# MySens-GWeasyRS485-Nano-005.net
KiCad netlist of a schematic drawn in EAGLE
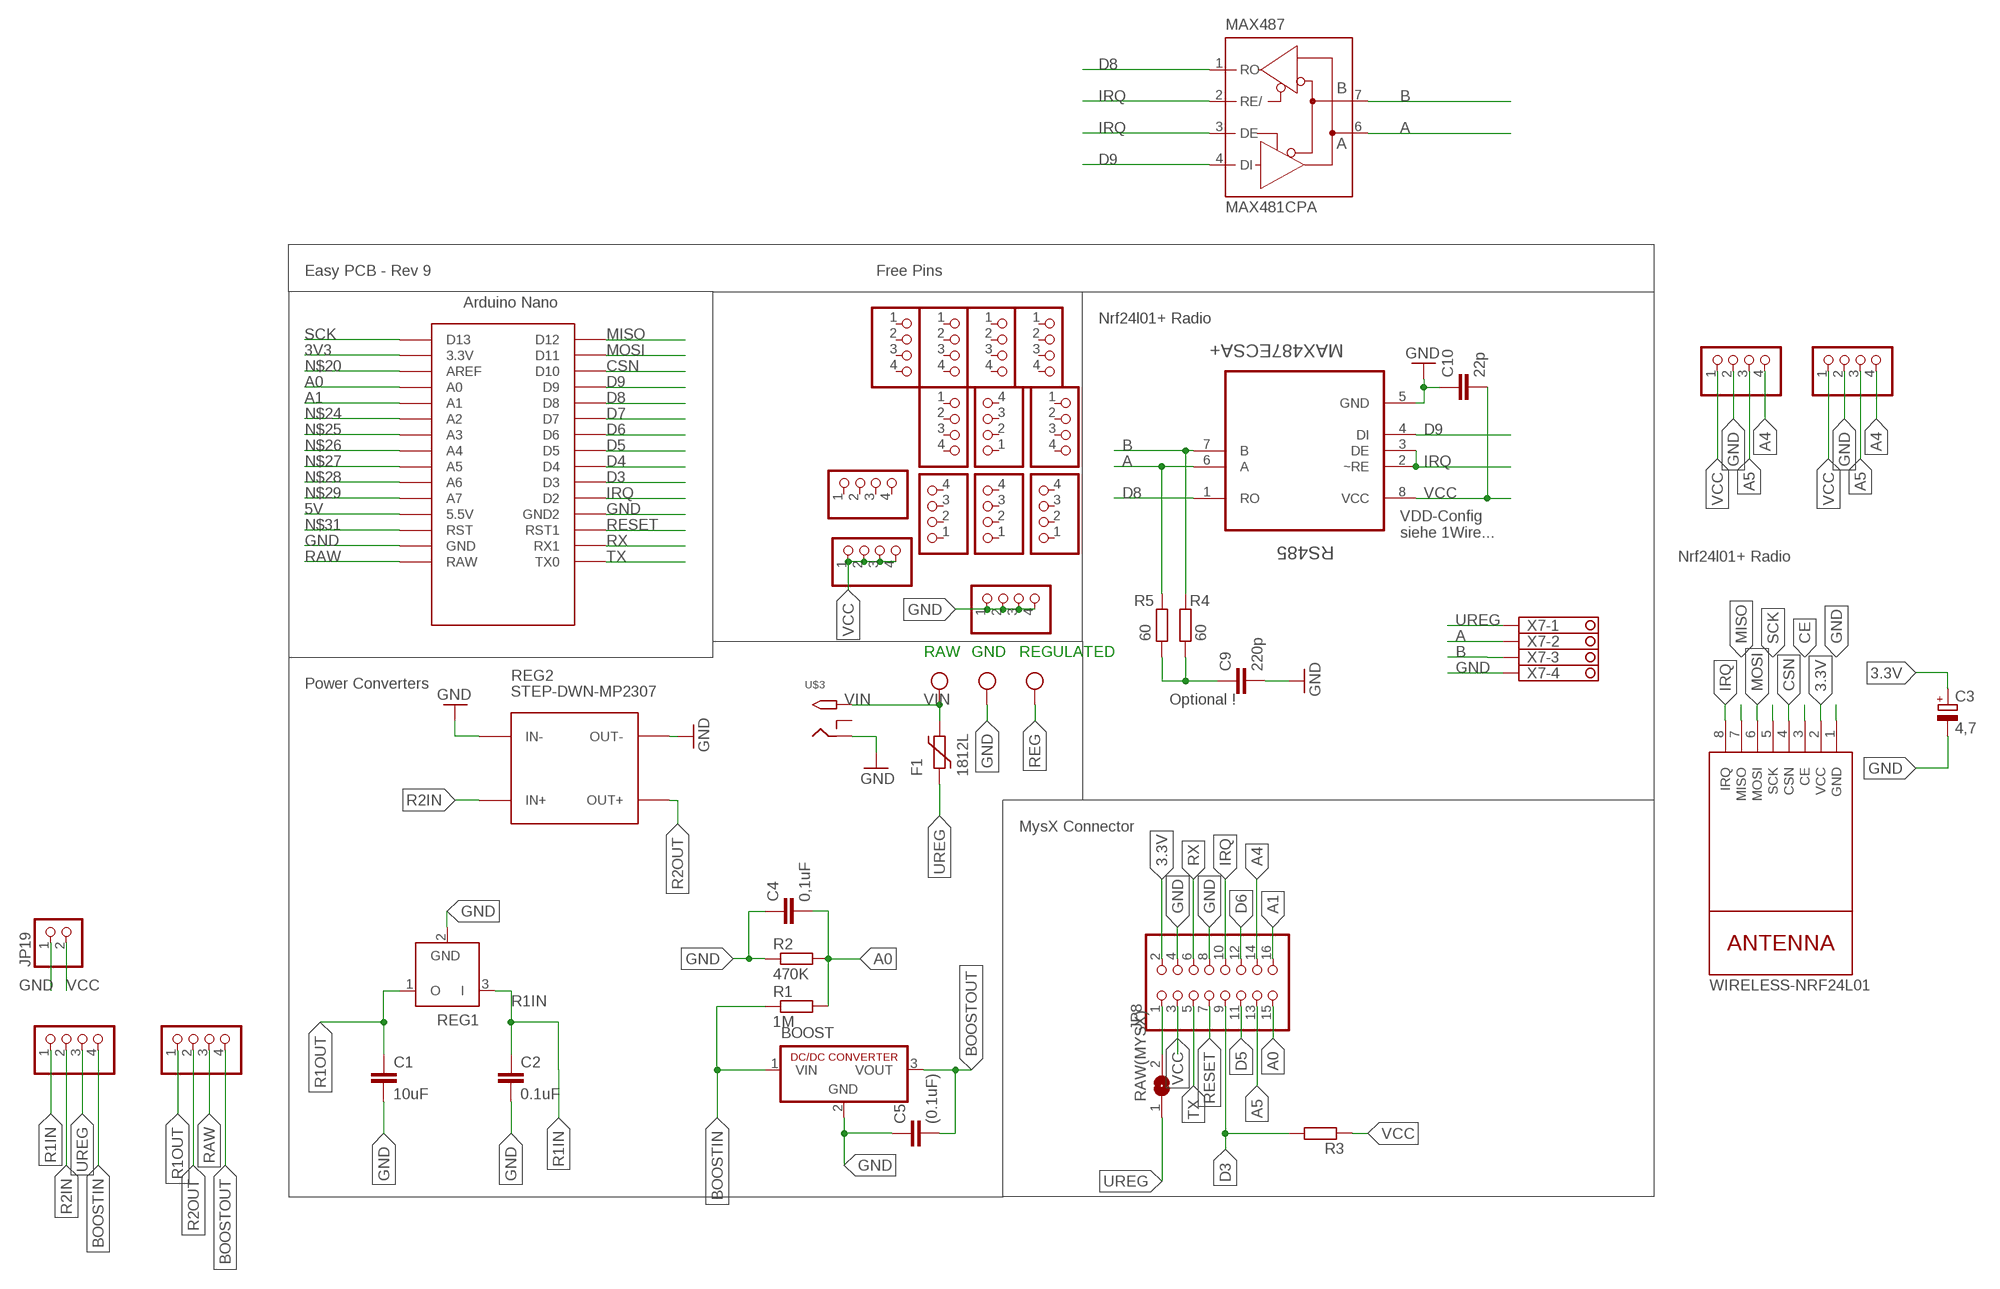
[diagram p0: schematic, sheet 1]

(export (version "E")
  (design (tool "Eeschema 10.0.6"))
  (components
    (comp (ref "BOOST")
      (value "R-78C1.8-1.0")
      (footprint "eagle-import:SIP3")
      (libsource (lib "eagle-import") (part "R-78C-1.01.8"))
    )
    (comp (ref "C1")
      (value "10uF")
      (footprint "eagle-import:C1210")
      (libsource (lib "eagle-import") (part "C-EUC1210"))
    )
    (comp (ref "C2")
      (value "0.1uF")
      (footprint "eagle-import:C1206")
      (libsource (lib "eagle-import") (part "C-EUC1206"))
    )
    (comp (ref "C3")
      (value "4,7")
      (footprint "eagle-import:SMC_C")
      (libsource (lib "eagle-import") (part "CPOL-EUSMCC"))
    )
    (comp (ref "C4")
      (value "0,1uF")
      (footprint "eagle-import:C1206")
      (libsource (lib "eagle-import") (part "C-EUC1206"))
    )
    (comp (ref "C5")
      (value "(0.1uF)")
      (footprint "eagle-import:C1206")
      (libsource (lib "eagle-import") (part "C-EUC1206"))
    )
    (comp (ref "C9")
      (value "220p")
      (footprint "eagle-import:C0805")
      (libsource (lib "eagle-import") (part "C-EUC0805"))
    )
    (comp (ref "C10")
      (value "22p")
      (footprint "eagle-import:C0805")
      (libsource (lib "eagle-import") (part "C-EUC0805"))
    )
    (comp (ref "F1")
      (value "1812L")
      (footprint "eagle-import:1812L")
      (libsource (lib "eagle-import") (part "1812L"))
    )
    (comp (ref "JP1")
      (value "PINHD-1X04_2.54-S")
      (footprint "eagle-import:1X04-S")
      (libsource (lib "eagle-import") (part "PINHD-1X04_2.54-S"))
    )
    (comp (ref "JP2")
      (value "PINHD-1X04_2.54-S")
      (footprint "eagle-import:1X04-S")
      (libsource (lib "eagle-import") (part "PINHD-1X04_2.54-S"))
    )
    (comp (ref "JP3")
      (value "PINHD-1X04_2.54-S")
      (footprint "eagle-import:1X04-S")
      (libsource (lib "eagle-import") (part "PINHD-1X04_2.54-S"))
    )
    (comp (ref "JP4")
      (value "PINHD-1X04_2.54-S")
      (footprint "eagle-import:1X04-S")
      (libsource (lib "eagle-import") (part "PINHD-1X04_2.54-S"))
    )
    (comp (ref "JP5")
      (value "PINHD-1X04_2.54-S")
      (footprint "eagle-import:1X04-S")
      (libsource (lib "eagle-import") (part "PINHD-1X04_2.54-S"))
    )
    (comp (ref "JP6")
      (value "PINHD-1X04_2.54-S")
      (footprint "eagle-import:1X04-S")
      (libsource (lib "eagle-import") (part "PINHD-1X04_2.54-S"))
    )
    (comp (ref "JP7")
      (value "PINHD-1X04_2.54-S")
      (footprint "eagle-import:1X04-S")
      (libsource (lib "eagle-import") (part "PINHD-1X04_2.54-S"))
    )
    (comp (ref "JP8")
      (value "PINHD-2X08_2.54")
      (footprint "eagle-import:2X08")
      (libsource (lib "eagle-import") (part "PINHD-2X08_2.54"))
    )
    (comp (ref "JP9")
      (value "PINHD-1X04_2.54-S")
      (footprint "eagle-import:1X04-S")
      (libsource (lib "eagle-import") (part "PINHD-1X04_2.54-S"))
    )
    (comp (ref "JP10")
      (value "PINHD-1X04_2.54-S")
      (footprint "eagle-import:1X04-S")
      (libsource (lib "eagle-import") (part "PINHD-1X04_2.54-S"))
    )
    (comp (ref "JP11")
      (value "PINHD-1X04_2.54-S")
      (footprint "eagle-import:1X04-S")
      (libsource (lib "eagle-import") (part "PINHD-1X04_2.54-S"))
    )
    (comp (ref "JP12")
      (value "PINHD-1X04_2.54-S")
      (footprint "eagle-import:1X04-S")
      (libsource (lib "eagle-import") (part "PINHD-1X04_2.54-S"))
    )
    (comp (ref "JP13")
      (value "PINHD-1X04_2.54-S")
      (footprint "eagle-import:1X04-S")
      (libsource (lib "eagle-import") (part "PINHD-1X04_2.54-S"))
    )
    (comp (ref "JP14")
      (value "PINHD-1X04_2.54-S")
      (footprint "eagle-import:1X04-S")
      (libsource (lib "eagle-import") (part "PINHD-1X04_2.54-S"))
    )
    (comp (ref "JP15")
      (value "PINHD-1X04_2.54-S")
      (footprint "eagle-import:1X04-S")
      (libsource (lib "eagle-import") (part "PINHD-1X04_2.54-S"))
    )
    (comp (ref "JP16")
      (value "PINHD-1X04_2.54-S")
      (footprint "eagle-import:1X04-S")
      (libsource (lib "eagle-import") (part "PINHD-1X04_2.54-S"))
    )
    (comp (ref "JP17")
      (value "PINHD-1X04_2.54-S")
      (footprint "eagle-import:1X04-S")
      (libsource (lib "eagle-import") (part "PINHD-1X04_2.54-S"))
    )
    (comp (ref "JP18")
      (value "PINHD-1X04_2.54-S")
      (footprint "eagle-import:1X04-S")
      (libsource (lib "eagle-import") (part "PINHD-1X04_2.54-S"))
    )
    (comp (ref "JP19")
      (value "PINHD-1X2")
      (footprint "eagle-import:1X02")
      (libsource (lib "eagle-import") (part "PINHD-1X2"))
    )
    (comp (ref "MAX487")
      (value "MAX481CPA")
      (footprint "eagle-import:DIL08")
      (libsource (lib "eagle-import") (part "MAX481CPA"))
    )
    (comp (ref "NRF24L01+")
      (value "WIRELESS-NRF24L01")
      (footprint "eagle-import:WIRELESS-NRF24L01")
      (libsource (lib "eagle-import") (part "WIRELESS-NRF24L01"))
    )
    (comp (ref "R1")
      (value "1M")
      (footprint "eagle-import:R0805")
      (libsource (lib "eagle-import") (part "R-EU_R0805"))
    )
    (comp (ref "R2")
      (value "470K")
      (footprint "eagle-import:R0805")
      (libsource (lib "eagle-import") (part "R-EU_R0805"))
    )
    (comp (ref "R3")
      (value "R-EU_R0805")
      (footprint "eagle-import:R0805")
      (libsource (lib "eagle-import") (part "R-EU_R0805"))
    )
    (comp (ref "R4")
      (value "60")
      (footprint "eagle-import:R0805")
      (libsource (lib "eagle-import") (part "R-EU_R0805"))
    )
    (comp (ref "R5")
      (value "60")
      (footprint "eagle-import:R0805")
      (libsource (lib "eagle-import") (part "R-EU_R0805"))
    )
    (comp (ref "RAW(MYSX)")
      (value "SJ")
      (footprint "eagle-import:SJ")
      (libsource (lib "eagle-import") (part "SJ"))
    )
    (comp (ref "REG1")
      (value "LP2950Z")
      (footprint "eagle-import:TO92")
      (libsource (lib "eagle-import") (part "LP2950Z"))
    )
    (comp (ref "REG2")
      (value "STEP-DWN-MP2307")
      (footprint "eagle-import:DC-DC-STEP-DOWN-MP2307")
      (libsource (lib "eagle-import") (part "DC-DC-STEP-DOWN-MP2307"))
    )
    (comp (ref "REGULATED")
      (value "W237-103")
      (footprint "eagle-import:W237-103")
      (fields (field (name "MPN") "237-103"))
      (libsource (lib "eagle-import") (part "W237-103"))
    )
    (comp (ref "RS485")
      (value "MAX487ECSA+")
      (footprint "eagle-import:SOIC127P600X175-8N")
      (libsource (lib "eagle-import") (part "MAX487ECSA+"))
    )
    (comp (ref "U$2")
      (value "NANO")
      (footprint "eagle-import:NANO")
      (libsource (lib "eagle-import") (part "NANO"))
    )
    (comp (ref "U$3")
      (value "2.1MMJACKTHM")
      (footprint "eagle-import:PJ-102A")
      (libsource (lib "eagle-import") (part "2.1MMJACKTHM"))
    )
    (comp (ref "X7")
      (value "1751264")
      (footprint "eagle-import:1751264")
      (libsource (lib "eagle-import") (part "1751264"))
    )
  )
  (nets
    (net (code "1") (name "/3V3") (class "Default")
      (node (ref "U$2") (pin "3.3V") (pinfunction "3.3V_3.3V") (pintype "bidirectional"))
    )
    (net (code "2") (name "/5V") (class "Default")
      (node (ref "U$2") (pin "5V") (pinfunction "5.5V_5V") (pintype "bidirectional"))
    )
    (net (code "3") (name "/A") (class "Default")
      (node (ref "MAX487") (pin "6") (pinfunction "A_6") (pintype "passive"))
      (node (ref "R5") (pin "2") (pinfunction "2_2") (pintype "passive"))
      (node (ref "RS485") (pin "6") (pinfunction "A_6") (pintype "bidirectional"))
      (node (ref "X7") (pin "2") (pinfunction "K_2") (pintype "passive"))
    )
    (net (code "4") (name "/B") (class "Default")
      (node (ref "MAX487") (pin "7") (pinfunction "B_7") (pintype "passive"))
      (node (ref "R4") (pin "2") (pinfunction "2_2") (pintype "passive"))
      (node (ref "RS485") (pin "7") (pinfunction "B_7") (pintype "bidirectional"))
      (node (ref "X7") (pin "3") (pinfunction "K_3") (pintype "passive"))
    )
    (net (code "5") (name "/D4") (class "Default")
      (node (ref "U$2") (pin "D4") (pinfunction "D4_D4") (pintype "bidirectional"))
    )
    (net (code "6") (name "/D7") (class "Default")
      (node (ref "U$2") (pin "D7") (pinfunction "D7_D7") (pintype "bidirectional"))
    )
    (net (code "7") (name "/D8") (class "Default")
      (node (ref "MAX487") (pin "1") (pinfunction "RO_1") (pintype "output"))
      (node (ref "RS485") (pin "1") (pinfunction "RO_1") (pintype "output"))
      (node (ref "U$2") (pin "D8") (pinfunction "D8_D8") (pintype "bidirectional"))
    )
    (net (code "8") (name "/D9") (class "Default")
      (node (ref "MAX487") (pin "4") (pinfunction "DI_4") (pintype "input"))
      (node (ref "RS485") (pin "4") (pinfunction "DI_4") (pintype "input"))
      (node (ref "U$2") (pin "D9") (pinfunction "D9_D9") (pintype "bidirectional"))
    )
    (net (code "9") (name "/N$20") (class "Default")
      (node (ref "U$2") (pin "AREF") (pinfunction "AREF_AREF") (pintype "bidirectional"))
    )
    (net (code "10") (name "/N$24") (class "Default")
      (node (ref "U$2") (pin "A2") (pinfunction "A2_A2") (pintype "bidirectional"))
    )
    (net (code "11") (name "/N$25") (class "Default")
      (node (ref "U$2") (pin "A3") (pinfunction "A3_A3") (pintype "bidirectional"))
    )
    (net (code "12") (name "/N$26") (class "Default")
      (node (ref "U$2") (pin "A4") (pinfunction "A4_A4") (pintype "bidirectional"))
    )
    (net (code "13") (name "/N$27") (class "Default")
      (node (ref "U$2") (pin "A5") (pinfunction "A5_A5") (pintype "bidirectional"))
    )
    (net (code "14") (name "/N$28") (class "Default")
      (node (ref "U$2") (pin "A6") (pinfunction "A6_A6") (pintype "bidirectional"))
    )
    (net (code "15") (name "/N$29") (class "Default")
      (node (ref "U$2") (pin "A7") (pinfunction "A7_A7") (pintype "bidirectional"))
    )
    (net (code "16") (name "/N$31") (class "Default")
      (node (ref "U$2") (pin "RST") (pinfunction "RST_RST") (pintype "bidirectional"))
    )
    (net (code "17") (name "/VIN") (class "Default")
      (node (ref "F1") (pin "P$2") (pinfunction "2_P$2") (pintype "passive"))
      (node (ref "REGULATED") (pin "3") (pinfunction "KL_3") (pintype "passive"))
      (node (ref "U$3") (pin "TIP") (pinfunction "TIP_TIP") (pintype "bidirectional"))
    )
    (net (code "18") (name "3.3V") (class "Default")
      (node (ref "C3") (pin "+") (pinfunction "+_+") (pintype "passive"))
      (node (ref "JP8") (pin "2") (pinfunction "2_2") (pintype "passive"))
      (node (ref "NRF24L01+") (pin "2") (pinfunction "VCC_2") (pintype "power_in"))
    )
    (net (code "19") (name "A0") (class "Default")
      (node (ref "C4") (pin "2") (pinfunction "2_2") (pintype "passive"))
      (node (ref "JP8") (pin "15") (pinfunction "15_15") (pintype "passive"))
      (node (ref "R1") (pin "2") (pinfunction "2_2") (pintype "passive"))
      (node (ref "R2") (pin "2") (pinfunction "2_2") (pintype "passive"))
      (node (ref "U$2") (pin "A0") (pinfunction "A0_A0") (pintype "bidirectional"))
    )
    (net (code "20") (name "A1") (class "Default")
      (node (ref "JP8") (pin "16") (pinfunction "16_16") (pintype "passive"))
      (node (ref "U$2") (pin "A1") (pinfunction "A1_A1") (pintype "bidirectional"))
    )
    (net (code "21") (name "A4") (class "Default")
      (node (ref "JP10") (pin "4") (pinfunction "4_4") (pintype "passive"))
      (node (ref "JP6") (pin "4") (pinfunction "4_4") (pintype "passive"))
      (node (ref "JP8") (pin "14") (pinfunction "14_14") (pintype "passive"))
    )
    (net (code "22") (name "A5") (class "Default")
      (node (ref "JP10") (pin "3") (pinfunction "3_3") (pintype "passive"))
      (node (ref "JP6") (pin "3") (pinfunction "3_3") (pintype "passive"))
      (node (ref "JP8") (pin "13") (pinfunction "13_13") (pintype "passive"))
    )
    (net (code "23") (name "BOOSTIN") (class "Default")
      (node (ref "BOOST") (pin "1") (pinfunction "VIN_1") (pintype "passive"))
      (node (ref "JP2") (pin "4") (pinfunction "4_4") (pintype "passive"))
      (node (ref "R1") (pin "1") (pinfunction "1_1") (pintype "passive"))
    )
    (net (code "24") (name "BOOSTOUT") (class "Default")
      (node (ref "BOOST") (pin "3") (pinfunction "VOUT_3") (pintype "passive"))
      (node (ref "C5") (pin "2") (pinfunction "2_2") (pintype "passive"))
      (node (ref "JP4") (pin "4") (pinfunction "4_4") (pintype "passive"))
    )
    (net (code "25") (name "CE") (class "Default")
      (node (ref "NRF24L01+") (pin "3") (pinfunction "CE_3") (pintype "bidirectional"))
    )
    (net (code "26") (name "CSN") (class "Default")
      (node (ref "NRF24L01+") (pin "4") (pinfunction "CSN_4") (pintype "bidirectional"))
      (node (ref "U$2") (pin "D10") (pinfunction "D10_D10") (pintype "bidirectional"))
    )
    (net (code "27") (name "D3") (class "Default")
      (node (ref "JP8") (pin "9") (pinfunction "9_9") (pintype "passive"))
      (node (ref "R3") (pin "2") (pinfunction "2_2") (pintype "passive"))
      (node (ref "U$2") (pin "D3") (pinfunction "D3_D3") (pintype "bidirectional"))
    )
    (net (code "28") (name "D5") (class "Default")
      (node (ref "JP8") (pin "11") (pinfunction "11_11") (pintype "passive"))
      (node (ref "U$2") (pin "D5") (pinfunction "D5_D5") (pintype "bidirectional"))
    )
    (net (code "29") (name "D6") (class "Default")
      (node (ref "JP8") (pin "12") (pinfunction "12_12") (pintype "passive"))
      (node (ref "U$2") (pin "D6") (pinfunction "D6_D6") (pintype "bidirectional"))
    )
    (net (code "30") (name "GND") (class "Default")
      (node (ref "BOOST") (pin "2") (pinfunction "GND_2") (pintype "passive"))
      (node (ref "C1") (pin "2") (pinfunction "2_2") (pintype "passive"))
      (node (ref "C10") (pin "1") (pinfunction "1_1") (pintype "passive"))
      (node (ref "C2") (pin "2") (pinfunction "2_2") (pintype "passive"))
      (node (ref "C3") (pin "-") (pinfunction "-_-") (pintype "passive"))
      (node (ref "C4") (pin "1") (pinfunction "1_1") (pintype "passive"))
      (node (ref "C5") (pin "1") (pinfunction "1_1") (pintype "passive"))
      (node (ref "C9") (pin "2") (pinfunction "2_2") (pintype "passive"))
      (node (ref "JP1") (pin "1") (pinfunction "1_1") (pintype "passive"))
      (node (ref "JP1") (pin "2") (pinfunction "2_2") (pintype "passive"))
      (node (ref "JP1") (pin "3") (pinfunction "3_3") (pintype "passive"))
      (node (ref "JP1") (pin "4") (pinfunction "4_4") (pintype "passive"))
      (node (ref "JP10") (pin "2") (pinfunction "2_2") (pintype "passive"))
      (node (ref "JP19") (pin "1") (pinfunction "1_1") (pintype "passive"))
      (node (ref "JP6") (pin "2") (pinfunction "2_2") (pintype "passive"))
      (node (ref "JP8") (pin "4") (pinfunction "4_4") (pintype "passive"))
      (node (ref "JP8") (pin "8") (pinfunction "8_8") (pintype "passive"))
      (node (ref "NRF24L01+") (pin "1") (pinfunction "GND_1") (pintype "power_in"))
      (node (ref "R2") (pin "1") (pinfunction "1_1") (pintype "passive"))
      (node (ref "REG1") (pin "2") (pinfunction "GND_2") (pintype "power_in"))
      (node (ref "REG2") (pin "IN-") (pinfunction "IN-_IN-") (pintype "bidirectional"))
      (node (ref "REG2") (pin "OUT-") (pinfunction "OUT-_OUT-") (pintype "bidirectional"))
      (node (ref "REGULATED") (pin "2") (pinfunction "KL_2") (pintype "passive"))
      (node (ref "RS485") (pin "5") (pinfunction "GND_5") (pintype "passive"))
      (node (ref "U$2") (pin "GND") (pinfunction "GND_GND") (pintype "bidirectional"))
      (node (ref "U$2") (pin "GND1") (pinfunction "GND2_GND1") (pintype "bidirectional"))
      (node (ref "U$3") (pin "RING") (pinfunction "RING_RING") (pintype "bidirectional"))
      (node (ref "X7") (pin "4") (pinfunction "K_4") (pintype "passive"))
    )
    (net (code "31") (name "IRQ") (class "Default")
      (node (ref "JP8") (pin "10") (pinfunction "10_10") (pintype "passive"))
      (node (ref "MAX487") (pin "2") (pinfunction "RE/_2") (pintype "input"))
      (node (ref "MAX487") (pin "3") (pinfunction "DE_3") (pintype "input"))
      (node (ref "NRF24L01+") (pin "8") (pinfunction "IRQ_8") (pintype "bidirectional"))
      (node (ref "RS485") (pin "2") (pinfunction "~{RE}_2") (pintype "input"))
      (node (ref "RS485") (pin "3") (pinfunction "DE_3") (pintype "input"))
      (node (ref "U$2") (pin "D2") (pinfunction "D2_D2") (pintype "bidirectional"))
    )
    (net (code "32") (name "MISO") (class "Default")
      (node (ref "NRF24L01+") (pin "7") (pinfunction "MISO_7") (pintype "bidirectional"))
      (node (ref "U$2") (pin "D12") (pinfunction "D12_D12") (pintype "bidirectional"))
    )
    (net (code "33") (name "MOSI") (class "Default")
      (node (ref "NRF24L01+") (pin "6") (pinfunction "MOSI_6") (pintype "bidirectional"))
      (node (ref "U$2") (pin "D11") (pinfunction "D11_D11") (pintype "bidirectional"))
    )
    (net (code "34") (name "Net-(C9-Pad1)") (class "Default")
      (node (ref "C9") (pin "1") (pinfunction "1_1") (pintype "passive"))
      (node (ref "R4") (pin "1") (pinfunction "1_1") (pintype "passive"))
      (node (ref "R5") (pin "1") (pinfunction "1_1") (pintype "passive"))
    )
    (net (code "35") (name "Net-(JP8-Pad1)") (class "Default")
      (node (ref "JP8") (pin "1") (pinfunction "1_1") (pintype "passive"))
      (node (ref "RAW(MYSX)") (pin "2") (pinfunction "2_2") (pintype "passive"))
    )
    (net (code "36") (name "R1IN") (class "Default")
      (node (ref "C2") (pin "1") (pinfunction "1_1") (pintype "passive"))
      (node (ref "JP2") (pin "1") (pinfunction "1_1") (pintype "passive"))
      (node (ref "REG1") (pin "3") (pinfunction "I_3") (pintype "input"))
    )
    (net (code "37") (name "R1OUT") (class "Default")
      (node (ref "C1") (pin "1") (pinfunction "1_1") (pintype "passive"))
      (node (ref "JP4") (pin "1") (pinfunction "1_1") (pintype "passive"))
      (node (ref "REG1") (pin "1") (pinfunction "O_1") (pintype "input"))
    )
    (net (code "38") (name "R2IN") (class "Default")
      (node (ref "JP2") (pin "2") (pinfunction "2_2") (pintype "passive"))
      (node (ref "REG2") (pin "IN+") (pinfunction "IN+_IN+") (pintype "bidirectional"))
    )
    (net (code "39") (name "R2OUT") (class "Default")
      (node (ref "JP4") (pin "2") (pinfunction "2_2") (pintype "passive"))
      (node (ref "REG2") (pin "OUT+") (pinfunction "OUT+_OUT+") (pintype "bidirectional"))
    )
    (net (code "40") (name "RAW") (class "Default")
      (node (ref "JP4") (pin "3") (pinfunction "3_3") (pintype "passive"))
      (node (ref "U$2") (pin "RAW") (pinfunction "RAW_RAW") (pintype "bidirectional"))
    )
    (net (code "41") (name "REG") (class "Default")
      (node (ref "REGULATED") (pin "1") (pinfunction "KL_1") (pintype "passive"))
    )
    (net (code "42") (name "RESET") (class "Default")
      (node (ref "JP8") (pin "7") (pinfunction "7_7") (pintype "passive"))
      (node (ref "U$2") (pin "RST1") (pinfunction "RST1_RST1") (pintype "bidirectional"))
    )
    (net (code "43") (name "RX") (class "Default")
      (node (ref "JP8") (pin "6") (pinfunction "6_6") (pintype "passive"))
      (node (ref "U$2") (pin "RX1") (pinfunction "RX1_RX1") (pintype "bidirectional"))
    )
    (net (code "44") (name "SCK") (class "Default")
      (node (ref "NRF24L01+") (pin "5") (pinfunction "SCK_5") (pintype "bidirectional"))
      (node (ref "U$2") (pin "D13") (pinfunction "D13_D13") (pintype "bidirectional"))
    )
    (net (code "45") (name "TX") (class "Default")
      (node (ref "JP8") (pin "5") (pinfunction "5_5") (pintype "passive"))
      (node (ref "U$2") (pin "TX0") (pinfunction "TX0_TX0") (pintype "bidirectional"))
    )
    (net (code "46") (name "UREG") (class "Default")
      (node (ref "F1") (pin "P$1") (pinfunction "1_P$1") (pintype "passive"))
      (node (ref "JP2") (pin "3") (pinfunction "3_3") (pintype "passive"))
      (node (ref "RAW(MYSX)") (pin "1") (pinfunction "1_1") (pintype "passive"))
      (node (ref "X7") (pin "1") (pinfunction "K_1") (pintype "passive"))
    )
    (net (code "47") (name "VCC") (class "Default")
      (node (ref "C10") (pin "2") (pinfunction "2_2") (pintype "passive"))
      (node (ref "JP10") (pin "1") (pinfunction "1_1") (pintype "passive"))
      (node (ref "JP19") (pin "2") (pinfunction "2_2") (pintype "passive"))
      (node (ref "JP3") (pin "1") (pinfunction "1_1") (pintype "passive"))
      (node (ref "JP3") (pin "2") (pinfunction "2_2") (pintype "passive"))
      (node (ref "JP3") (pin "3") (pinfunction "3_3") (pintype "passive"))
      (node (ref "JP3") (pin "4") (pinfunction "4_4") (pintype "passive"))
      (node (ref "JP6") (pin "1") (pinfunction "1_1") (pintype "passive"))
      (node (ref "JP8") (pin "3") (pinfunction "3_3") (pintype "passive"))
      (node (ref "R3") (pin "1") (pinfunction "1_1") (pintype "passive"))
      (node (ref "RS485") (pin "8") (pinfunction "VCC_8") (pintype "power_in"))
    )
    (net (code "48") (name "unconnected-(JP5-Pad1)") (class "Default")
      (node (ref "JP5") (pin "1") (pinfunction "1_1") (pintype "passive"))
    )
    (net (code "49") (name "unconnected-(JP5-Pad2)") (class "Default")
      (node (ref "JP5") (pin "2") (pinfunction "2_2") (pintype "passive"))
    )
    (net (code "50") (name "unconnected-(JP5-Pad3)") (class "Default")
      (node (ref "JP5") (pin "3") (pinfunction "3_3") (pintype "passive"))
    )
    (net (code "51") (name "unconnected-(JP5-Pad4)") (class "Default")
      (node (ref "JP5") (pin "4") (pinfunction "4_4") (pintype "passive"))
    )
    (net (code "52") (name "unconnected-(JP7-Pad1)") (class "Default")
      (node (ref "JP7") (pin "1") (pinfunction "1_1") (pintype "passive"))
    )
    (net (code "53") (name "unconnected-(JP7-Pad2)") (class "Default")
      (node (ref "JP7") (pin "2") (pinfunction "2_2") (pintype "passive"))
    )
    (net (code "54") (name "unconnected-(JP7-Pad3)") (class "Default")
      (node (ref "JP7") (pin "3") (pinfunction "3_3") (pintype "passive"))
    )
    (net (code "55") (name "unconnected-(JP7-Pad4)") (class "Default")
      (node (ref "JP7") (pin "4") (pinfunction "4_4") (pintype "passive"))
    )
    (net (code "56") (name "unconnected-(JP9-Pad1)") (class "Default")
      (node (ref "JP9") (pin "1") (pinfunction "1_1") (pintype "passive"))
    )
    (net (code "57") (name "unconnected-(JP9-Pad2)") (class "Default")
      (node (ref "JP9") (pin "2") (pinfunction "2_2") (pintype "passive"))
    )
    (net (code "58") (name "unconnected-(JP9-Pad3)") (class "Default")
      (node (ref "JP9") (pin "3") (pinfunction "3_3") (pintype "passive"))
    )
    (net (code "59") (name "unconnected-(JP9-Pad4)") (class "Default")
      (node (ref "JP9") (pin "4") (pinfunction "4_4") (pintype "passive"))
    )
    (net (code "60") (name "unconnected-(JP11-Pad1)") (class "Default")
      (node (ref "JP11") (pin "1") (pinfunction "1_1") (pintype "passive"))
    )
    (net (code "61") (name "unconnected-(JP11-Pad2)") (class "Default")
      (node (ref "JP11") (pin "2") (pinfunction "2_2") (pintype "passive"))
    )
    (net (code "62") (name "unconnected-(JP11-Pad3)") (class "Default")
      (node (ref "JP11") (pin "3") (pinfunction "3_3") (pintype "passive"))
    )
    (net (code "63") (name "unconnected-(JP11-Pad4)") (class "Default")
      (node (ref "JP11") (pin "4") (pinfunction "4_4") (pintype "passive"))
    )
    (net (code "64") (name "unconnected-(JP12-Pad1)") (class "Default")
      (node (ref "JP12") (pin "1") (pinfunction "1_1") (pintype "passive"))
    )
    (net (code "65") (name "unconnected-(JP12-Pad2)") (class "Default")
      (node (ref "JP12") (pin "2") (pinfunction "2_2") (pintype "passive"))
    )
    (net (code "66") (name "unconnected-(JP12-Pad3)") (class "Default")
      (node (ref "JP12") (pin "3") (pinfunction "3_3") (pintype "passive"))
    )
    (net (code "67") (name "unconnected-(JP12-Pad4)") (class "Default")
      (node (ref "JP12") (pin "4") (pinfunction "4_4") (pintype "passive"))
    )
    (net (code "68") (name "unconnected-(JP13-Pad1)") (class "Default")
      (node (ref "JP13") (pin "1") (pinfunction "1_1") (pintype "passive"))
    )
    (net (code "69") (name "unconnected-(JP13-Pad2)") (class "Default")
      (node (ref "JP13") (pin "2") (pinfunction "2_2") (pintype "passive"))
    )
    (net (code "70") (name "unconnected-(JP13-Pad3)") (class "Default")
      (node (ref "JP13") (pin "3") (pinfunction "3_3") (pintype "passive"))
    )
    (net (code "71") (name "unconnected-(JP13-Pad4)") (class "Default")
      (node (ref "JP13") (pin "4") (pinfunction "4_4") (pintype "passive"))
    )
    (net (code "72") (name "unconnected-(JP14-Pad1)") (class "Default")
      (node (ref "JP14") (pin "1") (pinfunction "1_1") (pintype "passive"))
    )
    (net (code "73") (name "unconnected-(JP14-Pad2)") (class "Default")
      (node (ref "JP14") (pin "2") (pinfunction "2_2") (pintype "passive"))
    )
    (net (code "74") (name "unconnected-(JP14-Pad3)") (class "Default")
      (node (ref "JP14") (pin "3") (pinfunction "3_3") (pintype "passive"))
    )
    (net (code "75") (name "unconnected-(JP14-Pad4)") (class "Default")
      (node (ref "JP14") (pin "4") (pinfunction "4_4") (pintype "passive"))
    )
    (net (code "76") (name "unconnected-(JP15-Pad1)") (class "Default")
      (node (ref "JP15") (pin "1") (pinfunction "1_1") (pintype "passive"))
    )
    (net (code "77") (name "unconnected-(JP15-Pad2)") (class "Default")
      (node (ref "JP15") (pin "2") (pinfunction "2_2") (pintype "passive"))
    )
    (net (code "78") (name "unconnected-(JP15-Pad3)") (class "Default")
      (node (ref "JP15") (pin "3") (pinfunction "3_3") (pintype "passive"))
    )
    (net (code "79") (name "unconnected-(JP15-Pad4)") (class "Default")
      (node (ref "JP15") (pin "4") (pinfunction "4_4") (pintype "passive"))
    )
    (net (code "80") (name "unconnected-(JP16-Pad1)") (class "Default")
      (node (ref "JP16") (pin "1") (pinfunction "1_1") (pintype "passive"))
    )
    (net (code "81") (name "unconnected-(JP16-Pad2)") (class "Default")
      (node (ref "JP16") (pin "2") (pinfunction "2_2") (pintype "passive"))
    )
    (net (code "82") (name "unconnected-(JP16-Pad3)") (class "Default")
      (node (ref "JP16") (pin "3") (pinfunction "3_3") (pintype "passive"))
    )
    (net (code "83") (name "unconnected-(JP16-Pad4)") (class "Default")
      (node (ref "JP16") (pin "4") (pinfunction "4_4") (pintype "passive"))
    )
    (net (code "84") (name "unconnected-(JP17-Pad1)") (class "Default")
      (node (ref "JP17") (pin "1") (pinfunction "1_1") (pintype "passive"))
    )
    (net (code "85") (name "unconnected-(JP17-Pad2)") (class "Default")
      (node (ref "JP17") (pin "2") (pinfunction "2_2") (pintype "passive"))
    )
    (net (code "86") (name "unconnected-(JP17-Pad3)") (class "Default")
      (node (ref "JP17") (pin "3") (pinfunction "3_3") (pintype "passive"))
    )
    (net (code "87") (name "unconnected-(JP17-Pad4)") (class "Default")
      (node (ref "JP17") (pin "4") (pinfunction "4_4") (pintype "passive"))
    )
    (net (code "88") (name "unconnected-(JP18-Pad1)") (class "Default")
      (node (ref "JP18") (pin "1") (pinfunction "1_1") (pintype "passive"))
    )
    (net (code "89") (name "unconnected-(JP18-Pad2)") (class "Default")
      (node (ref "JP18") (pin "2") (pinfunction "2_2") (pintype "passive"))
    )
    (net (code "90") (name "unconnected-(JP18-Pad3)") (class "Default")
      (node (ref "JP18") (pin "3") (pinfunction "3_3") (pintype "passive"))
    )
    (net (code "91") (name "unconnected-(JP18-Pad4)") (class "Default")
      (node (ref "JP18") (pin "4") (pinfunction "4_4") (pintype "passive"))
    )
    (net (code "92") (name "unconnected-(U$2-PadICSP1)") (class "Default")
      (node (ref "U$2") (pin "ICSP1") (pinfunction "ICSP1_ICSP1") (pintype "bidirectional"))
    )
    (net (code "93") (name "unconnected-(U$2-PadICSP2)") (class "Default")
      (node (ref "U$2") (pin "ICSP2") (pinfunction "ICSP2_ICSP2") (pintype "bidirectional"))
    )
    (net (code "94") (name "unconnected-(U$2-PadICSP3)") (class "Default")
      (node (ref "U$2") (pin "ICSP3") (pinfunction "ICSP3_ICSP3") (pintype "bidirectional"))
    )
    (net (code "95") (name "unconnected-(U$2-PadICSP4)") (class "Default")
      (node (ref "U$2") (pin "ICSP4") (pinfunction "ICSP4_ICSP4") (pintype "bidirectional"))
    )
    (net (code "96") (name "unconnected-(U$2-PadICSP5)") (class "Default")
      (node (ref "U$2") (pin "ICSP5") (pinfunction "ICSP5_ICSP5") (pintype "bidirectional"))
    )
    (net (code "97") (name "unconnected-(U$2-PadICSP6)") (class "Default")
      (node (ref "U$2") (pin "ICSP6") (pinfunction "ICSP6_ICSP6") (pintype "bidirectional"))
    )
    (net (code "98") (name "unconnected-(U$3-PadRING_SW)") (class "Default")
      (node (ref "U$3") (pin "RING_SW") (pinfunction "RING_SW_RING_SW") (pintype "bidirectional"))
    )
  )
)
